# spider.net
KiCad netlist of a schematic drawn in EAGLE
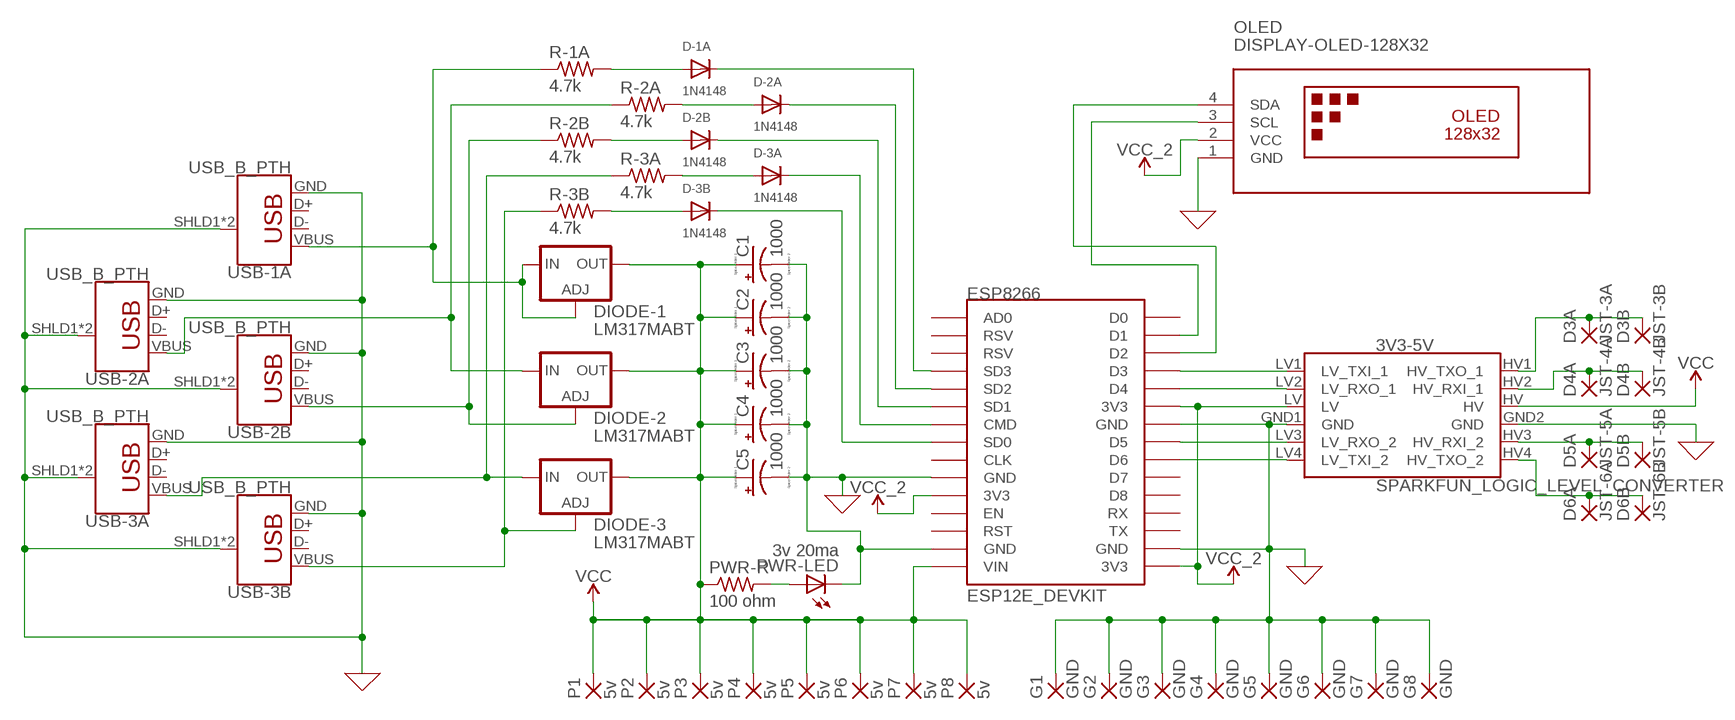
[diagram p0: schematic, sheet 1]

(export (version "E")
  (design (tool "Eeschema 10.0.6"))
  (components
    (comp (ref "3V3-5V")
      (value "SPARKFUN_LOGIC_LEVEL_CONVERTER")
      (footprint "eagle-import:SPARKFUN_LOGIC_LEVEL_CONVERTER")
      (libsource (lib "eagle-import") (part "SPARKFUN_LOGIC_LEVEL_CONVERTER"))
    )
    (comp (ref "C1")
      (value "1000")
      (footprint "eagle-import:E3,5-8")
      (libsource (lib "eagle-import") (part "CPOL-USE3.5-8"))
    )
    (comp (ref "C2")
      (value "1000")
      (footprint "eagle-import:E3,5-8")
      (libsource (lib "eagle-import") (part "CPOL-USE3.5-8"))
    )
    (comp (ref "C3")
      (value "1000")
      (footprint "eagle-import:E3,5-8")
      (libsource (lib "eagle-import") (part "CPOL-USE3.5-8"))
    )
    (comp (ref "C4")
      (value "1000")
      (footprint "eagle-import:E3,5-8")
      (libsource (lib "eagle-import") (part "CPOL-USE3.5-8"))
    )
    (comp (ref "C5")
      (value "1000")
      (footprint "eagle-import:E3,5-8")
      (libsource (lib "eagle-import") (part "CPOL-USE3.5-8"))
    )
    (comp (ref "D-1A")
      (value "1N4148")
      (footprint "eagle-import:DO-1N4148")
      (libsource (lib "eagle-import") (part "DIODEDO-1N4148"))
    )
    (comp (ref "D-2A")
      (value "1N4148")
      (footprint "eagle-import:DO-1N4148")
      (libsource (lib "eagle-import") (part "DIODEDO-1N4148"))
    )
    (comp (ref "D-2B")
      (value "1N4148")
      (footprint "eagle-import:DO-1N4148")
      (libsource (lib "eagle-import") (part "DIODEDO-1N4148"))
    )
    (comp (ref "D-3A")
      (value "1N4148")
      (footprint "eagle-import:DO-1N4148")
      (libsource (lib "eagle-import") (part "DIODEDO-1N4148"))
    )
    (comp (ref "D-3B")
      (value "1N4148")
      (footprint "eagle-import:DO-1N4148")
      (libsource (lib "eagle-import") (part "DIODEDO-1N4148"))
    )
    (comp (ref "D3A")
      (value "JST-3A")
      (footprint "eagle-import:2,54_1,1")
      (libsource (lib "eagle-import") (part "2,54/1,1"))
    )
    (comp (ref "D3B")
      (value "JST-3B")
      (footprint "eagle-import:2,54_1,1")
      (libsource (lib "eagle-import") (part "2,54/1,1"))
    )
    (comp (ref "D4A")
      (value "JST-4A")
      (footprint "eagle-import:2,54_1,1")
      (libsource (lib "eagle-import") (part "2,54/1,1"))
    )
    (comp (ref "D4B")
      (value "JST-4B")
      (footprint "eagle-import:2,54_1,1")
      (libsource (lib "eagle-import") (part "2,54/1,1"))
    )
    (comp (ref "D5A")
      (value "JST-5A")
      (footprint "eagle-import:2,54_1,1")
      (libsource (lib "eagle-import") (part "2,54/1,1"))
    )
    (comp (ref "D5B")
      (value "JST-5B")
      (footprint "eagle-import:2,54_1,1")
      (libsource (lib "eagle-import") (part "2,54/1,1"))
    )
    (comp (ref "D6A")
      (value "JST-6A")
      (footprint "eagle-import:2,54_1,1")
      (libsource (lib "eagle-import") (part "2,54/1,1"))
    )
    (comp (ref "D6B")
      (value "JST-6B")
      (footprint "eagle-import:2,54_1,1")
      (libsource (lib "eagle-import") (part "2,54/1,1"))
    )
    (comp (ref "DIODE-1")
      (value "LM317MABT")
      (footprint "eagle-import:TO220L1")
      (libsource (lib "eagle-import") (part "LM317?MABT"))
    )
    (comp (ref "DIODE-2")
      (value "LM317MABT")
      (footprint "eagle-import:TO220L1")
      (libsource (lib "eagle-import") (part "LM317?MABT"))
    )
    (comp (ref "DIODE-3")
      (value "LM317MABT")
      (footprint "eagle-import:TO220L1")
      (libsource (lib "eagle-import") (part "LM317?MABT"))
    )
    (comp (ref "ESP8266")
      (value "ESP12E_DEVKIT")
      (footprint "eagle-import:ESP12E_DEVKIT")
      (libsource (lib "eagle-import") (part "ESP12E_DEVKIT"))
    )
    (comp (ref "G1")
      (value "GND")
      (footprint "eagle-import:2,54_1,1")
      (libsource (lib "eagle-import") (part "2,54/1,1"))
    )
    (comp (ref "G2")
      (value "GND")
      (footprint "eagle-import:2,54_1,1")
      (libsource (lib "eagle-import") (part "2,54/1,1"))
    )
    (comp (ref "G3")
      (value "GND")
      (footprint "eagle-import:2,54_1,1")
      (libsource (lib "eagle-import") (part "2,54/1,1"))
    )
    (comp (ref "G4")
      (value "GND")
      (footprint "eagle-import:2,54_1,1")
      (libsource (lib "eagle-import") (part "2,54/1,1"))
    )
    (comp (ref "G5")
      (value "GND")
      (footprint "eagle-import:2,54_1,1")
      (libsource (lib "eagle-import") (part "2,54/1,1"))
    )
    (comp (ref "G6")
      (value "GND")
      (footprint "eagle-import:2,54_1,1")
      (libsource (lib "eagle-import") (part "2,54/1,1"))
    )
    (comp (ref "G7")
      (value "GND")
      (footprint "eagle-import:2,54_1,1")
      (libsource (lib "eagle-import") (part "2,54/1,1"))
    )
    (comp (ref "G8")
      (value "GND")
      (footprint "eagle-import:2,54_1,1")
      (libsource (lib "eagle-import") (part "2,54/1,1"))
    )
    (comp (ref "OLED")
      (value "DISPLAY-OLED-128X32")
      (footprint "eagle-import:DISPLAY-OLED-128X32")
      (libsource (lib "eagle-import") (part "DISPLAY-OLED-128X32"))
    )
    (comp (ref "P1")
      (value "5v")
      (footprint "eagle-import:2,54_1,1")
      (libsource (lib "eagle-import") (part "2,54/1,1"))
    )
    (comp (ref "P2")
      (value "5v")
      (footprint "eagle-import:2,54_1,1")
      (libsource (lib "eagle-import") (part "2,54/1,1"))
    )
    (comp (ref "P3")
      (value "5v")
      (footprint "eagle-import:2,54_1,1")
      (libsource (lib "eagle-import") (part "2,54/1,1"))
    )
    (comp (ref "P4")
      (value "5v")
      (footprint "eagle-import:2,54_1,1")
      (libsource (lib "eagle-import") (part "2,54/1,1"))
    )
    (comp (ref "P5")
      (value "5v")
      (footprint "eagle-import:2,54_1,1")
      (libsource (lib "eagle-import") (part "2,54/1,1"))
    )
    (comp (ref "P6")
      (value "5v")
      (footprint "eagle-import:2,54_1,1")
      (libsource (lib "eagle-import") (part "2,54/1,1"))
    )
    (comp (ref "P7")
      (value "5v")
      (footprint "eagle-import:2,54_1,1")
      (libsource (lib "eagle-import") (part "2,54/1,1"))
    )
    (comp (ref "P8")
      (value "5v")
      (footprint "eagle-import:2,54_1,1")
      (libsource (lib "eagle-import") (part "2,54/1,1"))
    )
    (comp (ref "PWR-LED")
      (value "3v 20ma")
      (footprint "eagle-import:LED3MM")
      (libsource (lib "eagle-import") (part "LED3MM"))
    )
    (comp (ref "PWR-R")
      (value "100 ohm")
      (footprint "eagle-import:0204_7")
      (libsource (lib "eagle-import") (part "R-US_0204/7"))
    )
    (comp (ref "R-1A")
      (value "4.7k")
      (footprint "eagle-import:0207_7")
      (libsource (lib "eagle-import") (part "R-US_0207/7"))
    )
    (comp (ref "R-2A")
      (value "4.7k")
      (footprint "eagle-import:0207_7")
      (libsource (lib "eagle-import") (part "R-US_0207/7"))
    )
    (comp (ref "R-2B")
      (value "4.7k")
      (footprint "eagle-import:0207_7")
      (libsource (lib "eagle-import") (part "R-US_0207/7"))
    )
    (comp (ref "R-3A")
      (value "4.7k")
      (footprint "eagle-import:0207_7")
      (libsource (lib "eagle-import") (part "R-US_0207/7"))
    )
    (comp (ref "R-3B")
      (value "4.7k")
      (footprint "eagle-import:0207_7")
      (libsource (lib "eagle-import") (part "R-US_0207/7"))
    )
    (comp (ref "USB-1A")
      (value "USB_B_PTH")
      (footprint "eagle-import:USB-B-PTH")
      (libsource (lib "eagle-import") (part "USB_B_PTH"))
    )
    (comp (ref "USB-2A")
      (value "USB_B_PTH")
      (footprint "eagle-import:USB-B-PTH")
      (libsource (lib "eagle-import") (part "USB_B_PTH"))
    )
    (comp (ref "USB-2B")
      (value "USB_B_PTH")
      (footprint "eagle-import:USB-B-PTH")
      (libsource (lib "eagle-import") (part "USB_B_PTH"))
    )
    (comp (ref "USB-3A")
      (value "USB_B_PTH")
      (footprint "eagle-import:USB-B-PTH")
      (libsource (lib "eagle-import") (part "USB_B_PTH"))
    )
    (comp (ref "USB-3B")
      (value "USB_B_PTH")
      (footprint "eagle-import:USB-B-PTH")
      (libsource (lib "eagle-import") (part "USB_B_PTH"))
    )
  )
  (nets
    (net (code "1") (name "GND") (class "Default")
      (node (ref "3V3-5V") (pin "GND1") (pinfunction "GND_GND1") (pintype "power_in"))
      (node (ref "3V3-5V") (pin "GND2") (pinfunction "GND_GND2") (pintype "power_in"))
      (node (ref "C1") (pin "-") (pinfunction "-_-") (pintype "passive"))
      (node (ref "C2") (pin "-") (pinfunction "-_-") (pintype "passive"))
      (node (ref "C3") (pin "-") (pinfunction "-_-") (pintype "passive"))
      (node (ref "C4") (pin "-") (pinfunction "-_-") (pintype "passive"))
      (node (ref "C5") (pin "-") (pinfunction "-_-") (pintype "passive"))
      (node (ref "ESP8266") (pin "GND@0") (pinfunction "GND_GND@0") (pintype "bidirectional"))
      (node (ref "ESP8266") (pin "GND@1") (pinfunction "GND_GND@1") (pintype "bidirectional"))
      (node (ref "ESP8266") (pin "GND@2") (pinfunction "GND_GND@2") (pintype "bidirectional"))
      (node (ref "ESP8266") (pin "GND@3") (pinfunction "GND_GND@3") (pintype "bidirectional"))
      (node (ref "G1") (pin "1") (pinfunction "P_1") (pintype "passive"))
      (node (ref "G2") (pin "1") (pinfunction "P_1") (pintype "passive"))
      (node (ref "G3") (pin "1") (pinfunction "P_1") (pintype "passive"))
      (node (ref "G4") (pin "1") (pinfunction "P_1") (pintype "passive"))
      (node (ref "G5") (pin "1") (pinfunction "P_1") (pintype "passive"))
      (node (ref "G6") (pin "1") (pinfunction "P_1") (pintype "passive"))
      (node (ref "G7") (pin "1") (pinfunction "P_1") (pintype "passive"))
      (node (ref "G8") (pin "1") (pinfunction "P_1") (pintype "passive"))
      (node (ref "OLED") (pin "1") (pinfunction "GND_1") (pintype "power_in"))
      (node (ref "PWR-LED") (pin "K") (pinfunction "C_K") (pintype "passive"))
      (node (ref "USB-1A") (pin "GND") (pinfunction "GND_GND") (pintype "power_in"))
      (node (ref "USB-1A") (pin "SHLD1") (pinfunction "SHIELD_SHLD1") (pintype "bidirectional"))
      (node (ref "USB-1A") (pin "SHLD2") (pinfunction "SHIELD_SHLD2") (pintype "bidirectional"))
      (node (ref "USB-2A") (pin "GND") (pinfunction "GND_GND") (pintype "power_in"))
      (node (ref "USB-2A") (pin "SHLD1") (pinfunction "SHIELD_SHLD1") (pintype "bidirectional"))
      (node (ref "USB-2A") (pin "SHLD2") (pinfunction "SHIELD_SHLD2") (pintype "bidirectional"))
      (node (ref "USB-2B") (pin "GND") (pinfunction "GND_GND") (pintype "power_in"))
      (node (ref "USB-2B") (pin "SHLD1") (pinfunction "SHIELD_SHLD1") (pintype "bidirectional"))
      (node (ref "USB-2B") (pin "SHLD2") (pinfunction "SHIELD_SHLD2") (pintype "bidirectional"))
      (node (ref "USB-3A") (pin "GND") (pinfunction "GND_GND") (pintype "power_in"))
      (node (ref "USB-3A") (pin "SHLD1") (pinfunction "SHIELD_SHLD1") (pintype "bidirectional"))
      (node (ref "USB-3A") (pin "SHLD2") (pinfunction "SHIELD_SHLD2") (pintype "bidirectional"))
      (node (ref "USB-3B") (pin "GND") (pinfunction "GND_GND") (pintype "power_in"))
      (node (ref "USB-3B") (pin "SHLD1") (pinfunction "SHIELD_SHLD1") (pintype "bidirectional"))
      (node (ref "USB-3B") (pin "SHLD2") (pinfunction "SHIELD_SHLD2") (pintype "bidirectional"))
    )
    (net (code "2") (name "Net-(3V3-5V-HV_RXI_1)") (class "Default")
      (node (ref "3V3-5V") (pin "HV2") (pinfunction "HV_RXI_1_HV2") (pintype "bidirectional"))
      (node (ref "D4A") (pin "1") (pinfunction "P_1") (pintype "passive"))
      (node (ref "D4B") (pin "1") (pinfunction "P_1") (pintype "passive"))
    )
    (net (code "3") (name "Net-(3V3-5V-HV_RXI_2)") (class "Default")
      (node (ref "3V3-5V") (pin "HV3") (pinfunction "HV_RXI_2_HV3") (pintype "bidirectional"))
      (node (ref "D5A") (pin "1") (pinfunction "P_1") (pintype "passive"))
      (node (ref "D5B") (pin "1") (pinfunction "P_1") (pintype "passive"))
    )
    (net (code "4") (name "Net-(3V3-5V-HV_TXO_1)") (class "Default")
      (node (ref "3V3-5V") (pin "HV1") (pinfunction "HV_TXO_1_HV1") (pintype "bidirectional"))
      (node (ref "D3A") (pin "1") (pinfunction "P_1") (pintype "passive"))
      (node (ref "D3B") (pin "1") (pinfunction "P_1") (pintype "passive"))
    )
    (net (code "5") (name "Net-(3V3-5V-HV_TXO_2)") (class "Default")
      (node (ref "3V3-5V") (pin "HV4") (pinfunction "HV_TXO_2_HV4") (pintype "bidirectional"))
      (node (ref "D6A") (pin "1") (pinfunction "P_1") (pintype "passive"))
      (node (ref "D6B") (pin "1") (pinfunction "P_1") (pintype "passive"))
    )
    (net (code "6") (name "Net-(3V3-5V-LV_RXO_1)") (class "Default")
      (node (ref "3V3-5V") (pin "LV2") (pinfunction "LV_RXO_1_LV2") (pintype "bidirectional"))
      (node (ref "ESP8266") (pin "D4") (pinfunction "D4_D4") (pintype "bidirectional"))
    )
    (net (code "7") (name "Net-(3V3-5V-LV_RXO_2)") (class "Default")
      (node (ref "3V3-5V") (pin "LV3") (pinfunction "LV_RXO_2_LV3") (pintype "bidirectional"))
      (node (ref "ESP8266") (pin "D5") (pinfunction "D5_D5") (pintype "bidirectional"))
    )
    (net (code "8") (name "Net-(3V3-5V-LV_TXI_1)") (class "Default")
      (node (ref "3V3-5V") (pin "LV1") (pinfunction "LV_TXI_1_LV1") (pintype "bidirectional"))
      (node (ref "ESP8266") (pin "D3") (pinfunction "D3_D3") (pintype "bidirectional"))
    )
    (net (code "9") (name "Net-(3V3-5V-LV_TXI_2)") (class "Default")
      (node (ref "3V3-5V") (pin "LV4") (pinfunction "LV_TXI_2_LV4") (pintype "bidirectional"))
      (node (ref "ESP8266") (pin "D6") (pinfunction "D6_D6") (pintype "bidirectional"))
    )
    (net (code "10") (name "Net-(D-1A-PadA)") (class "Default")
      (node (ref "D-1A") (pin "A") (pinfunction "A_A") (pintype "passive"))
      (node (ref "R-1A") (pin "2") (pinfunction "2_2") (pintype "passive"))
    )
    (net (code "11") (name "Net-(D-1A-PadC)") (class "Default")
      (node (ref "D-1A") (pin "C") (pinfunction "C_C") (pintype "passive"))
      (node (ref "ESP8266") (pin "SD3") (pinfunction "SD3_SD3") (pintype "bidirectional"))
    )
    (net (code "12") (name "Net-(D-2A-PadA)") (class "Default")
      (node (ref "D-2A") (pin "A") (pinfunction "A_A") (pintype "passive"))
      (node (ref "R-2A") (pin "2") (pinfunction "2_2") (pintype "passive"))
    )
    (net (code "13") (name "Net-(D-2A-PadC)") (class "Default")
      (node (ref "D-2A") (pin "C") (pinfunction "C_C") (pintype "passive"))
      (node (ref "ESP8266") (pin "SD2") (pinfunction "SD2_SD2") (pintype "bidirectional"))
    )
    (net (code "14") (name "Net-(D-2B-PadA)") (class "Default")
      (node (ref "D-2B") (pin "A") (pinfunction "A_A") (pintype "passive"))
      (node (ref "R-2B") (pin "2") (pinfunction "2_2") (pintype "passive"))
    )
    (net (code "15") (name "Net-(D-2B-PadC)") (class "Default")
      (node (ref "D-2B") (pin "C") (pinfunction "C_C") (pintype "passive"))
      (node (ref "ESP8266") (pin "SD1") (pinfunction "SD1_SD1") (pintype "bidirectional"))
    )
    (net (code "16") (name "Net-(D-3A-PadA)") (class "Default")
      (node (ref "D-3A") (pin "A") (pinfunction "A_A") (pintype "passive"))
      (node (ref "R-3A") (pin "2") (pinfunction "2_2") (pintype "passive"))
    )
    (net (code "17") (name "Net-(D-3A-PadC)") (class "Default")
      (node (ref "D-3A") (pin "C") (pinfunction "C_C") (pintype "passive"))
      (node (ref "ESP8266") (pin "CMD") (pinfunction "CMD_CMD") (pintype "bidirectional"))
    )
    (net (code "18") (name "Net-(D-3B-PadA)") (class "Default")
      (node (ref "D-3B") (pin "A") (pinfunction "A_A") (pintype "passive"))
      (node (ref "R-3B") (pin "2") (pinfunction "2_2") (pintype "passive"))
    )
    (net (code "19") (name "Net-(D-3B-PadC)") (class "Default")
      (node (ref "D-3B") (pin "C") (pinfunction "C_C") (pintype "passive"))
      (node (ref "ESP8266") (pin "SD0") (pinfunction "SD0_SD0") (pintype "bidirectional"))
    )
    (net (code "20") (name "Net-(DIODE-1-ADJ)") (class "Default")
      (node (ref "DIODE-1") (pin "1") (pinfunction "ADJ_1") (pintype "input"))
      (node (ref "DIODE-1") (pin "3") (pinfunction "IN_3") (pintype "input"))
      (node (ref "R-1A") (pin "1") (pinfunction "1_1") (pintype "passive"))
      (node (ref "USB-1A") (pin "VBUS") (pinfunction "VBUS_VBUS") (pintype "power_in"))
    )
    (net (code "21") (name "Net-(DIODE-2-ADJ)") (class "Default")
      (node (ref "DIODE-2") (pin "1") (pinfunction "ADJ_1") (pintype "input"))
      (node (ref "R-2B") (pin "1") (pinfunction "1_1") (pintype "passive"))
      (node (ref "USB-2B") (pin "VBUS") (pinfunction "VBUS_VBUS") (pintype "power_in"))
    )
    (net (code "22") (name "Net-(DIODE-2-IN)") (class "Default")
      (node (ref "DIODE-2") (pin "3") (pinfunction "IN_3") (pintype "input"))
      (node (ref "R-2A") (pin "1") (pinfunction "1_1") (pintype "passive"))
      (node (ref "USB-2A") (pin "VBUS") (pinfunction "VBUS_VBUS") (pintype "power_in"))
    )
    (net (code "23") (name "Net-(DIODE-3-ADJ)") (class "Default")
      (node (ref "DIODE-3") (pin "1") (pinfunction "ADJ_1") (pintype "input"))
      (node (ref "R-3B") (pin "1") (pinfunction "1_1") (pintype "passive"))
      (node (ref "USB-3B") (pin "VBUS") (pinfunction "VBUS_VBUS") (pintype "power_in"))
    )
    (net (code "24") (name "Net-(DIODE-3-IN)") (class "Default")
      (node (ref "DIODE-3") (pin "3") (pinfunction "IN_3") (pintype "input"))
      (node (ref "R-3A") (pin "1") (pinfunction "1_1") (pintype "passive"))
      (node (ref "USB-3A") (pin "VBUS") (pinfunction "VBUS_VBUS") (pintype "power_in"))
    )
    (net (code "25") (name "Net-(OLED-SCL)") (class "Default")
      (node (ref "ESP8266") (pin "D1") (pinfunction "D1_D1") (pintype "bidirectional"))
      (node (ref "OLED") (pin "3") (pinfunction "SCL_3") (pintype "bidirectional"))
    )
    (net (code "26") (name "Net-(OLED-SDA)") (class "Default")
      (node (ref "ESP8266") (pin "D2") (pinfunction "D2_D2") (pintype "bidirectional"))
      (node (ref "OLED") (pin "4") (pinfunction "SDA_4") (pintype "bidirectional"))
    )
    (net (code "27") (name "Net-(PWR-LED-PadA)") (class "Default")
      (node (ref "PWR-LED") (pin "A") (pinfunction "A_A") (pintype "passive"))
      (node (ref "PWR-R") (pin "2") (pinfunction "2_2") (pintype "passive"))
    )
    (net (code "28") (name "VCC") (class "Default")
      (node (ref "3V3-5V") (pin "HV") (pinfunction "HV_HV") (pintype "power_in"))
      (node (ref "C1") (pin "+") (pinfunction "+_+") (pintype "passive"))
      (node (ref "C2") (pin "+") (pinfunction "+_+") (pintype "passive"))
      (node (ref "C3") (pin "+") (pinfunction "+_+") (pintype "passive"))
      (node (ref "C4") (pin "+") (pinfunction "+_+") (pintype "passive"))
      (node (ref "C5") (pin "+") (pinfunction "+_+") (pintype "passive"))
      (node (ref "DIODE-1") (pin "2") (pinfunction "OUT_2") (pintype "passive"))
      (node (ref "DIODE-2") (pin "2") (pinfunction "OUT_2") (pintype "passive"))
      (node (ref "DIODE-3") (pin "2") (pinfunction "OUT_2") (pintype "passive"))
      (node (ref "ESP8266") (pin "VIN") (pinfunction "VIN_VIN") (pintype "bidirectional"))
      (node (ref "P1") (pin "1") (pinfunction "P_1") (pintype "passive"))
      (node (ref "P2") (pin "1") (pinfunction "P_1") (pintype "passive"))
      (node (ref "P3") (pin "1") (pinfunction "P_1") (pintype "passive"))
      (node (ref "P4") (pin "1") (pinfunction "P_1") (pintype "passive"))
      (node (ref "P5") (pin "1") (pinfunction "P_1") (pintype "passive"))
      (node (ref "P6") (pin "1") (pinfunction "P_1") (pintype "passive"))
      (node (ref "P7") (pin "1") (pinfunction "P_1") (pintype "passive"))
      (node (ref "P8") (pin "1") (pinfunction "P_1") (pintype "passive"))
      (node (ref "PWR-R") (pin "1") (pinfunction "1_1") (pintype "passive"))
    )
    (net (code "29") (name "VCC_2") (class "Default")
      (node (ref "3V3-5V") (pin "LV") (pinfunction "LV_LV") (pintype "power_in"))
      (node (ref "ESP8266") (pin "3V3@0") (pinfunction "3V3_3V3@0") (pintype "bidirectional"))
      (node (ref "ESP8266") (pin "3V3@1") (pinfunction "3V3_3V3@1") (pintype "bidirectional"))
      (node (ref "ESP8266") (pin "3V3@2") (pinfunction "3V3_3V3@2") (pintype "bidirectional"))
      (node (ref "OLED") (pin "2") (pinfunction "VCC_2") (pintype "power_in"))
    )
    (net (code "30") (name "unconnected-(ESP8266-PadAD0)") (class "Default")
      (node (ref "ESP8266") (pin "AD0") (pinfunction "AD0_AD0") (pintype "bidirectional"))
    )
    (net (code "31") (name "unconnected-(ESP8266-PadCLK)") (class "Default")
      (node (ref "ESP8266") (pin "CLK") (pinfunction "CLK_CLK") (pintype "bidirectional"))
    )
    (net (code "32") (name "unconnected-(ESP8266-PadD0)") (class "Default")
      (node (ref "ESP8266") (pin "D0") (pinfunction "D0_D0") (pintype "bidirectional"))
    )
    (net (code "33") (name "unconnected-(ESP8266-PadD7)") (class "Default")
      (node (ref "ESP8266") (pin "D7") (pinfunction "D7_D7") (pintype "bidirectional"))
    )
    (net (code "34") (name "unconnected-(ESP8266-PadD8)") (class "Default")
      (node (ref "ESP8266") (pin "D8") (pinfunction "D8_D8") (pintype "bidirectional"))
    )
    (net (code "35") (name "unconnected-(ESP8266-PadEN)") (class "Default")
      (node (ref "ESP8266") (pin "EN") (pinfunction "EN_EN") (pintype "bidirectional"))
    )
    (net (code "36") (name "unconnected-(ESP8266-PadRST)") (class "Default")
      (node (ref "ESP8266") (pin "RST") (pinfunction "RST_RST") (pintype "bidirectional"))
    )
    (net (code "37") (name "unconnected-(ESP8266-PadRX)") (class "Default")
      (node (ref "ESP8266") (pin "RX") (pinfunction "RX_RX") (pintype "bidirectional"))
    )
    (net (code "38") (name "unconnected-(ESP8266-PadTX)") (class "Default")
      (node (ref "ESP8266") (pin "TX") (pinfunction "TX_TX") (pintype "bidirectional"))
    )
    (net (code "39") (name "unconnected-(ESP8266-RSV-PadRSV@0)") (class "Default")
      (node (ref "ESP8266") (pin "RSV@0") (pinfunction "RSV_RSV@0") (pintype "bidirectional"))
    )
    (net (code "40") (name "unconnected-(ESP8266-RSV-PadRSV@1)") (class "Default")
      (node (ref "ESP8266") (pin "RSV@1") (pinfunction "RSV_RSV@1") (pintype "bidirectional"))
    )
    (net (code "41") (name "unconnected-(USB-1A-PadD+)") (class "Default")
      (node (ref "USB-1A") (pin "D+") (pinfunction "D+_D+") (pintype "bidirectional"))
    )
    (net (code "42") (name "unconnected-(USB-1A-PadD-)") (class "Default")
      (node (ref "USB-1A") (pin "D-") (pinfunction "D-_D-") (pintype "bidirectional"))
    )
    (net (code "43") (name "unconnected-(USB-2A-PadD+)") (class "Default")
      (node (ref "USB-2A") (pin "D+") (pinfunction "D+_D+") (pintype "bidirectional"))
    )
    (net (code "44") (name "unconnected-(USB-2A-PadD-)") (class "Default")
      (node (ref "USB-2A") (pin "D-") (pinfunction "D-_D-") (pintype "bidirectional"))
    )
    (net (code "45") (name "unconnected-(USB-2B-PadD+)") (class "Default")
      (node (ref "USB-2B") (pin "D+") (pinfunction "D+_D+") (pintype "bidirectional"))
    )
    (net (code "46") (name "unconnected-(USB-2B-PadD-)") (class "Default")
      (node (ref "USB-2B") (pin "D-") (pinfunction "D-_D-") (pintype "bidirectional"))
    )
    (net (code "47") (name "unconnected-(USB-3A-PadD+)") (class "Default")
      (node (ref "USB-3A") (pin "D+") (pinfunction "D+_D+") (pintype "bidirectional"))
    )
    (net (code "48") (name "unconnected-(USB-3A-PadD-)") (class "Default")
      (node (ref "USB-3A") (pin "D-") (pinfunction "D-_D-") (pintype "bidirectional"))
    )
    (net (code "49") (name "unconnected-(USB-3B-PadD+)") (class "Default")
      (node (ref "USB-3B") (pin "D+") (pinfunction "D+_D+") (pintype "bidirectional"))
    )
    (net (code "50") (name "unconnected-(USB-3B-PadD-)") (class "Default")
      (node (ref "USB-3B") (pin "D-") (pinfunction "D-_D-") (pintype "bidirectional"))
    )
  )
)
